# main.net
KiCad netlist of a schematic drawn in Altium Designer
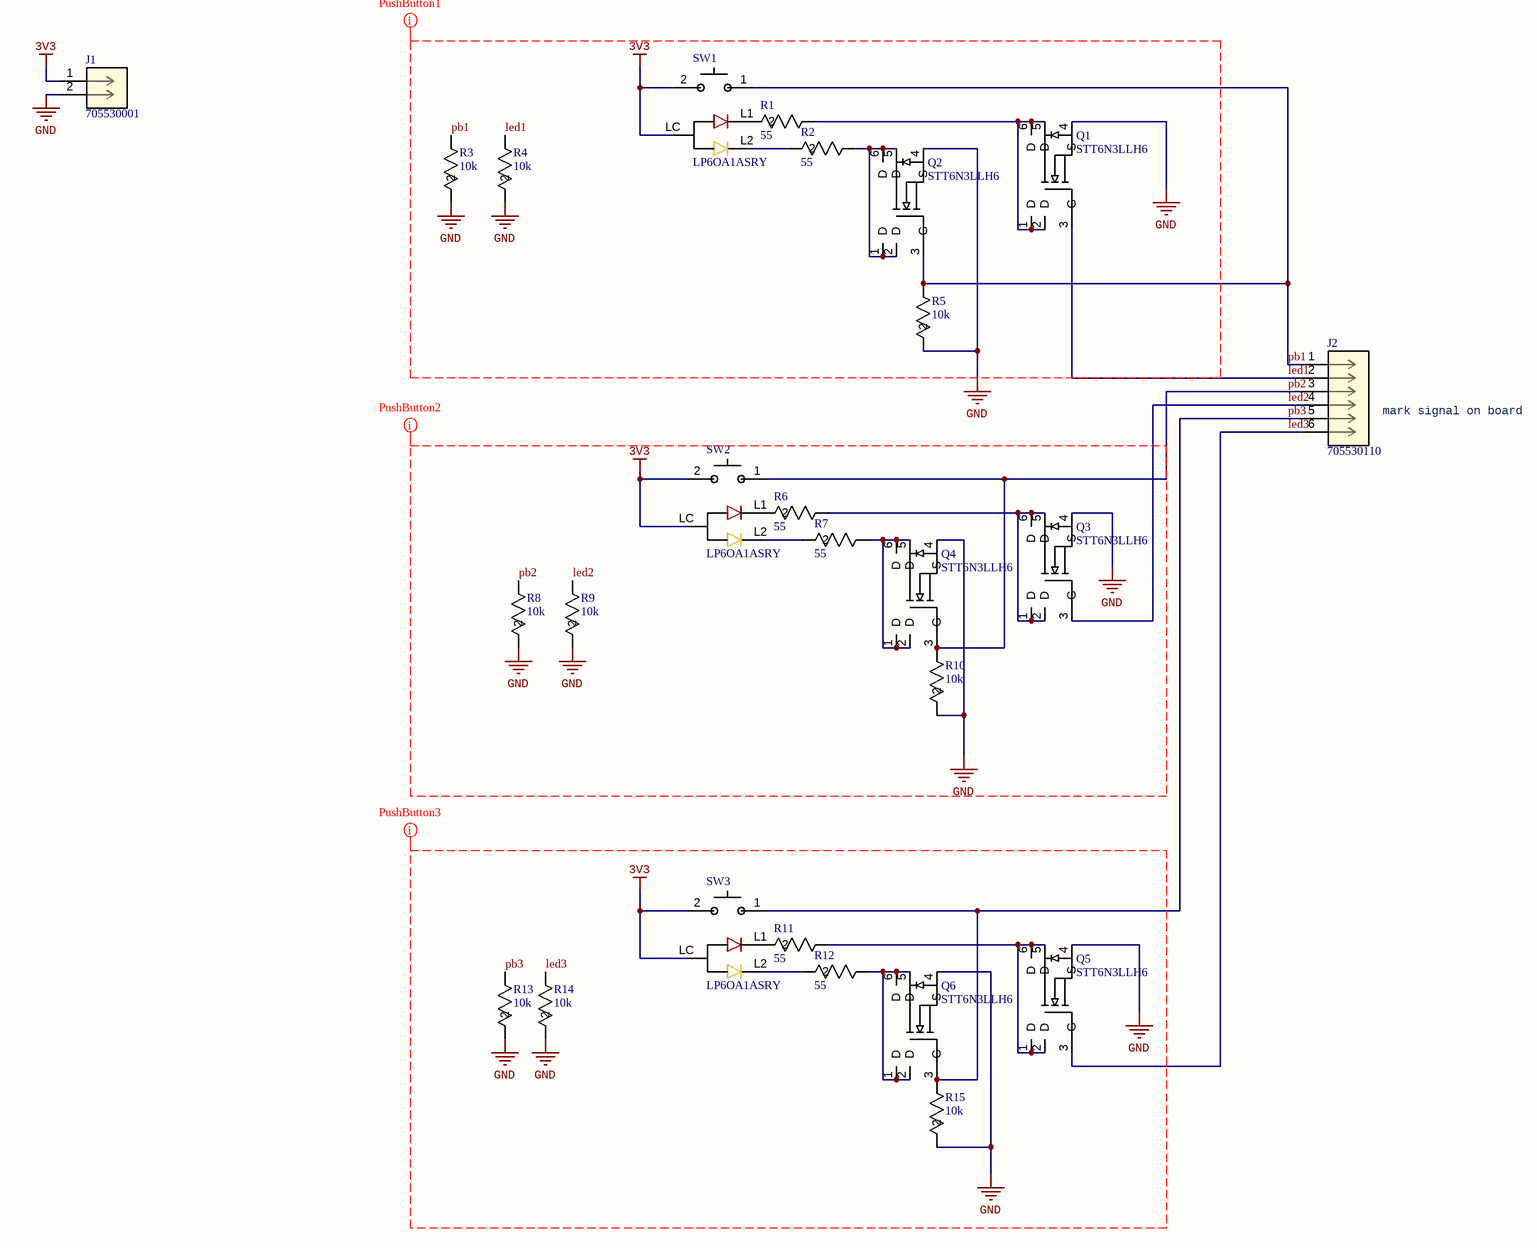
[diagram p0: main.SchDoc]

(export (version "E")
  (design (tool "Eeschema 10.0.6"))
  (components
    (comp (ref "J1")
      (value "705530001")
      (footprint "CONN_705530001_02_MOL")
      (fields (field (name "COPYRIGHT") "Copyright (C) 2025 Ultra Librarian. All rights reserved."))
      (libsource (lib "705530001") (part "705530001"))
    )
    (comp (ref "J2")
      (value "705530110")
      (footprint "CONN_705530005_06_MOL")
      (fields (field (name "COPYRIGHT") "Copyright (C) 2025 Ultra Librarian. All rights reserved."))
      (libsource (lib "705530110") (part "705530110"))
    )
    (comp (ref "Q1")
      (value "STT6N3LLH6")
      (footprint "SOT_6N3LLH6_STM")
      (description "N-channel 30 V, 0.021 Ohm, 6 A STripFET(TM) VI DeepGATE(TM) Power MOSFET in SOT23-6L package")
      (fields (field (name "COPYRIGHT") "Copyright (C) 2026 Ultra Librarian. All rights reserved."))
      (libsource (lib "STT6N3LLH6") (part "STT6N3LLH6"))
    )
    (comp (ref "Q2")
      (value "STT6N3LLH6")
      (footprint "SOT_6N3LLH6_STM")
      (description "N-channel 30 V, 0.021 Ohm, 6 A STripFET(TM) VI DeepGATE(TM) Power MOSFET in SOT23-6L package")
      (fields (field (name "COPYRIGHT") "Copyright (C) 2026 Ultra Librarian. All rights reserved."))
      (libsource (lib "STT6N3LLH6") (part "STT6N3LLH6"))
    )
    (comp (ref "Q3")
      (value "STT6N3LLH6")
      (footprint "SOT_6N3LLH6_STM")
      (description "N-channel 30 V, 0.021 Ohm, 6 A STripFET(TM) VI DeepGATE(TM) Power MOSFET in SOT23-6L package")
      (fields (field (name "COPYRIGHT") "Copyright (C) 2026 Ultra Librarian. All rights reserved."))
      (libsource (lib "STT6N3LLH6") (part "STT6N3LLH6"))
    )
    (comp (ref "Q4")
      (value "STT6N3LLH6")
      (footprint "SOT_6N3LLH6_STM")
      (description "N-channel 30 V, 0.021 Ohm, 6 A STripFET(TM) VI DeepGATE(TM) Power MOSFET in SOT23-6L package")
      (fields (field (name "COPYRIGHT") "Copyright (C) 2026 Ultra Librarian. All rights reserved."))
      (libsource (lib "STT6N3LLH6") (part "STT6N3LLH6"))
    )
    (comp (ref "Q5")
      (value "STT6N3LLH6")
      (footprint "SOT_6N3LLH6_STM")
      (description "N-channel 30 V, 0.021 Ohm, 6 A STripFET(TM) VI DeepGATE(TM) Power MOSFET in SOT23-6L package")
      (fields (field (name "COPYRIGHT") "Copyright (C) 2026 Ultra Librarian. All rights reserved."))
      (libsource (lib "STT6N3LLH6") (part "STT6N3LLH6"))
    )
    (comp (ref "Q6")
      (value "STT6N3LLH6")
      (footprint "SOT_6N3LLH6_STM")
      (description "N-channel 30 V, 0.021 Ohm, 6 A STripFET(TM) VI DeepGATE(TM) Power MOSFET in SOT23-6L package")
      (fields (field (name "COPYRIGHT") "Copyright (C) 2026 Ultra Librarian. All rights reserved."))
      (libsource (lib "STT6N3LLH6") (part "STT6N3LLH6"))
    )
    (comp (ref "R1")
      (value "55")
      (footprint "RC0603N_YAG")
      (description "55 OHM 0.1% 1/10W 0603")
      (fields
        (field (name "MANUFACTURER_PART_NUMBER") "0603 55Ohm")
        (field (name "COPYRIGHT") "Copyright (C) 2026 Ultra Librarian. All rights reserved.")
      )
      (libsource (lib "RT0603BRE07475RL") (part "0603 55Ohm"))
    )
    (comp (ref "R2")
      (value "55")
      (footprint "RC0603N_YAG")
      (description "55 OHM 0.1% 1/10W 0603")
      (fields
        (field (name "MANUFACTURER_PART_NUMBER") "0603 55Ohm")
        (field (name "COPYRIGHT") "Copyright (C) 2026 Ultra Librarian. All rights reserved.")
      )
      (libsource (lib "RT0603BRE07475RL") (part "0603 55Ohm"))
    )
    (comp (ref "R3")
      (value "10k")
      (footprint "RC0603N_YAG")
      (description "10K OHM 0.1% 1/10W 0603")
      (fields
        (field (name "MANUFACTURER_PART_NUMBER") "RT0603BRD0710KL")
        (field (name "COPYRIGHT") "Copyright (C) 2026 Ultra Librarian. All rights reserved.")
      )
      (libsource (lib "RT0603BRE07475RL") (part "RT0603BRD0710KL"))
    )
    (comp (ref "R4")
      (value "10k")
      (footprint "RC0603N_YAG")
      (description "10K OHM 0.1% 1/10W 0603")
      (fields
        (field (name "MANUFACTURER_PART_NUMBER") "RT0603BRD0710KL")
        (field (name "COPYRIGHT") "Copyright (C) 2026 Ultra Librarian. All rights reserved.")
      )
      (libsource (lib "RT0603BRE07475RL") (part "RT0603BRD0710KL"))
    )
    (comp (ref "R5")
      (value "10k")
      (footprint "RC0603N_YAG")
      (description "10K OHM 0.1% 1/10W 0603")
      (fields
        (field (name "MANUFACTURER_PART_NUMBER") "RT0603BRD0710KL")
        (field (name "COPYRIGHT") "Copyright (C) 2026 Ultra Librarian. All rights reserved.")
      )
      (libsource (lib "RT0603BRE07475RL") (part "RT0603BRD0710KL"))
    )
    (comp (ref "R6")
      (value "55")
      (footprint "RC0603N_YAG")
      (description "55 OHM 0.1% 1/10W 0603")
      (fields
        (field (name "MANUFACTURER_PART_NUMBER") "0603 55Ohm")
        (field (name "COPYRIGHT") "Copyright (C) 2026 Ultra Librarian. All rights reserved.")
      )
      (libsource (lib "RT0603BRE07475RL") (part "0603 55Ohm"))
    )
    (comp (ref "R7")
      (value "55")
      (footprint "RC0603N_YAG")
      (description "55 OHM 0.1% 1/10W 0603")
      (fields
        (field (name "MANUFACTURER_PART_NUMBER") "0603 55Ohm")
        (field (name "COPYRIGHT") "Copyright (C) 2026 Ultra Librarian. All rights reserved.")
      )
      (libsource (lib "RT0603BRE07475RL") (part "0603 55Ohm"))
    )
    (comp (ref "R8")
      (value "10k")
      (footprint "RC0603N_YAG")
      (description "10K OHM 0.1% 1/10W 0603")
      (fields
        (field (name "MANUFACTURER_PART_NUMBER") "RT0603BRD0710KL")
        (field (name "COPYRIGHT") "Copyright (C) 2026 Ultra Librarian. All rights reserved.")
      )
      (libsource (lib "RT0603BRE07475RL") (part "RT0603BRD0710KL"))
    )
    (comp (ref "R9")
      (value "10k")
      (footprint "RC0603N_YAG")
      (description "10K OHM 0.1% 1/10W 0603")
      (fields
        (field (name "MANUFACTURER_PART_NUMBER") "RT0603BRD0710KL")
        (field (name "COPYRIGHT") "Copyright (C) 2026 Ultra Librarian. All rights reserved.")
      )
      (libsource (lib "RT0603BRE07475RL") (part "RT0603BRD0710KL"))
    )
    (comp (ref "R10")
      (value "10k")
      (footprint "RC0603N_YAG")
      (description "10K OHM 0.1% 1/10W 0603")
      (fields
        (field (name "MANUFACTURER_PART_NUMBER") "RT0603BRD0710KL")
        (field (name "COPYRIGHT") "Copyright (C) 2026 Ultra Librarian. All rights reserved.")
      )
      (libsource (lib "RT0603BRE07475RL") (part "RT0603BRD0710KL"))
    )
    (comp (ref "R11")
      (value "55")
      (footprint "RC0603N_YAG")
      (description "55 OHM 0.1% 1/10W 0603")
      (fields
        (field (name "MANUFACTURER_PART_NUMBER") "0603 55Ohm")
        (field (name "COPYRIGHT") "Copyright (C) 2026 Ultra Librarian. All rights reserved.")
      )
      (libsource (lib "RT0603BRE07475RL") (part "0603 55Ohm"))
    )
    (comp (ref "R12")
      (value "55")
      (footprint "RC0603N_YAG")
      (description "55 OHM 0.1% 1/10W 0603")
      (fields
        (field (name "MANUFACTURER_PART_NUMBER") "0603 55Ohm")
        (field (name "COPYRIGHT") "Copyright (C) 2026 Ultra Librarian. All rights reserved.")
      )
      (libsource (lib "RT0603BRE07475RL") (part "0603 55Ohm"))
    )
    (comp (ref "R13")
      (value "10k")
      (footprint "RC0603N_YAG")
      (description "10K OHM 0.1% 1/10W 0603")
      (fields
        (field (name "MANUFACTURER_PART_NUMBER") "RT0603BRD0710KL")
        (field (name "COPYRIGHT") "Copyright (C) 2026 Ultra Librarian. All rights reserved.")
      )
      (libsource (lib "RT0603BRE07475RL") (part "RT0603BRD0710KL"))
    )
    (comp (ref "R14")
      (value "10k")
      (footprint "RC0603N_YAG")
      (description "10K OHM 0.1% 1/10W 0603")
      (fields
        (field (name "MANUFACTURER_PART_NUMBER") "RT0603BRD0710KL")
        (field (name "COPYRIGHT") "Copyright (C) 2026 Ultra Librarian. All rights reserved.")
      )
      (libsource (lib "RT0603BRE07475RL") (part "RT0603BRD0710KL"))
    )
    (comp (ref "R15")
      (value "10k")
      (footprint "RC0603N_YAG")
      (description "10K OHM 0.1% 1/10W 0603")
      (fields
        (field (name "MANUFACTURER_PART_NUMBER") "RT0603BRD0710KL")
        (field (name "COPYRIGHT") "Copyright (C) 2026 Ultra Librarian. All rights reserved.")
      )
      (libsource (lib "RT0603BRE07475RL") (part "RT0603BRD0710KL"))
    )
    (comp (ref "SW1")
      (value "LP6OA1ASRY")
      (footprint "LP6")
      (description "LP6 Series Illuminated Pushbutton Switch Momentary SPST Red/Yellow")
      (libsource (lib "LP6OA1ASRY") (part "LP6OA1ASRY"))
    )
    (comp (ref "SW2")
      (value "LP6OA1ASRY")
      (footprint "LP6")
      (description "LP6 Series Illuminated Pushbutton Switch Momentary SPST Red/Yellow")
      (libsource (lib "LP6OA1ASRY") (part "LP6OA1ASRY"))
    )
    (comp (ref "SW3")
      (value "LP6OA1ASRY")
      (footprint "LP6")
      (description "LP6 Series Illuminated Pushbutton Switch Momentary SPST Red/Yellow")
      (libsource (lib "LP6OA1ASRY") (part "LP6OA1ASRY"))
    )
  )
  (nets
    (net (code "1") (name "/led1") (class "Default")
      (node (ref "J2") (pin "2") (pinfunction "2_2") (pintype "passive"))
      (node (ref "Q1") (pin "3") (pinfunction "G_3") (pintype "passive"))
      (node (ref "R4") (pin "1") (pinfunction "1_1") (pintype "passive"))
    )
    (net (code "2") (name "/led2") (class "Default")
      (node (ref "J2") (pin "4") (pinfunction "4_4") (pintype "passive"))
      (node (ref "Q3") (pin "3") (pinfunction "G_3") (pintype "passive"))
      (node (ref "R9") (pin "1") (pinfunction "1_1") (pintype "passive"))
    )
    (net (code "3") (name "/led3") (class "Default")
      (node (ref "J2") (pin "6") (pinfunction "6_6") (pintype "passive"))
      (node (ref "Q5") (pin "3") (pinfunction "G_3") (pintype "passive"))
      (node (ref "R14") (pin "1") (pinfunction "1_1") (pintype "passive"))
    )
    (net (code "4") (name "/pb1") (class "Default")
      (node (ref "J2") (pin "1") (pinfunction "1_1") (pintype "passive"))
      (node (ref "Q2") (pin "3") (pinfunction "G_3") (pintype "passive"))
      (node (ref "R3") (pin "1") (pinfunction "1_1") (pintype "passive"))
      (node (ref "R5") (pin "1") (pinfunction "1_1") (pintype "passive"))
      (node (ref "SW1") (pin "1") (pintype "passive"))
    )
    (net (code "5") (name "/pb2") (class "Default")
      (node (ref "J2") (pin "3") (pinfunction "3_3") (pintype "passive"))
      (node (ref "Q4") (pin "3") (pinfunction "G_3") (pintype "passive"))
      (node (ref "R10") (pin "1") (pinfunction "1_1") (pintype "passive"))
      (node (ref "R8") (pin "1") (pinfunction "1_1") (pintype "passive"))
      (node (ref "SW2") (pin "1") (pintype "passive"))
    )
    (net (code "6") (name "/pb3") (class "Default")
      (node (ref "J2") (pin "5") (pinfunction "5_5") (pintype "passive"))
      (node (ref "Q6") (pin "3") (pinfunction "G_3") (pintype "passive"))
      (node (ref "R13") (pin "1") (pinfunction "1_1") (pintype "passive"))
      (node (ref "R15") (pin "1") (pinfunction "1_1") (pintype "passive"))
      (node (ref "SW3") (pin "1") (pintype "passive"))
    )
    (net (code "7") (name "3V3") (class "Default")
      (node (ref "J1") (pin "1") (pinfunction "1_1") (pintype "passive"))
      (node (ref "SW1") (pin "2") (pintype "passive"))
      (node (ref "SW1") (pin "LC") (pinfunction "red_LC") (pintype "passive"))
      (node (ref "SW2") (pin "2") (pintype "passive"))
      (node (ref "SW2") (pin "LC") (pinfunction "red_LC") (pintype "passive"))
      (node (ref "SW3") (pin "2") (pintype "passive"))
      (node (ref "SW3") (pin "LC") (pinfunction "red_LC") (pintype "passive"))
    )
    (net (code "8") (name "GND") (class "Default")
      (node (ref "J1") (pin "2") (pinfunction "2_2") (pintype "passive"))
      (node (ref "Q1") (pin "4") (pinfunction "S_4") (pintype "passive"))
      (node (ref "Q2") (pin "4") (pinfunction "S_4") (pintype "passive"))
      (node (ref "Q3") (pin "4") (pinfunction "S_4") (pintype "passive"))
      (node (ref "Q4") (pin "4") (pinfunction "S_4") (pintype "passive"))
      (node (ref "Q5") (pin "4") (pinfunction "S_4") (pintype "passive"))
      (node (ref "Q6") (pin "4") (pinfunction "S_4") (pintype "passive"))
      (node (ref "R10") (pin "2") (pinfunction "2_2") (pintype "passive"))
      (node (ref "R13") (pin "2") (pinfunction "2_2") (pintype "passive"))
      (node (ref "R14") (pin "2") (pinfunction "2_2") (pintype "passive"))
      (node (ref "R15") (pin "2") (pinfunction "2_2") (pintype "passive"))
      (node (ref "R3") (pin "2") (pinfunction "2_2") (pintype "passive"))
      (node (ref "R4") (pin "2") (pinfunction "2_2") (pintype "passive"))
      (node (ref "R5") (pin "2") (pinfunction "2_2") (pintype "passive"))
      (node (ref "R8") (pin "2") (pinfunction "2_2") (pintype "passive"))
      (node (ref "R9") (pin "2") (pinfunction "2_2") (pintype "passive"))
    )
    (net (code "9") (name "Net-(Q1-D-Pad1)") (class "Default")
      (node (ref "Q1") (pin "1") (pinfunction "D_1") (pintype "passive"))
      (node (ref "Q1") (pin "2") (pinfunction "D_2") (pintype "passive"))
      (node (ref "Q1") (pin "5") (pinfunction "D_5") (pintype "passive"))
      (node (ref "Q1") (pin "6") (pinfunction "D_6") (pintype "passive"))
      (node (ref "R1") (pin "1") (pinfunction "1_1") (pintype "passive"))
    )
    (net (code "10") (name "Net-(Q2-D-Pad1)") (class "Default")
      (node (ref "Q2") (pin "1") (pinfunction "D_1") (pintype "passive"))
      (node (ref "Q2") (pin "2") (pinfunction "D_2") (pintype "passive"))
      (node (ref "Q2") (pin "5") (pinfunction "D_5") (pintype "passive"))
      (node (ref "Q2") (pin "6") (pinfunction "D_6") (pintype "passive"))
      (node (ref "R2") (pin "1") (pinfunction "1_1") (pintype "passive"))
    )
    (net (code "11") (name "Net-(Q3-D-Pad1)") (class "Default")
      (node (ref "Q3") (pin "1") (pinfunction "D_1") (pintype "passive"))
      (node (ref "Q3") (pin "2") (pinfunction "D_2") (pintype "passive"))
      (node (ref "Q3") (pin "5") (pinfunction "D_5") (pintype "passive"))
      (node (ref "Q3") (pin "6") (pinfunction "D_6") (pintype "passive"))
      (node (ref "R6") (pin "1") (pinfunction "1_1") (pintype "passive"))
    )
    (net (code "12") (name "Net-(Q4-D-Pad1)") (class "Default")
      (node (ref "Q4") (pin "1") (pinfunction "D_1") (pintype "passive"))
      (node (ref "Q4") (pin "2") (pinfunction "D_2") (pintype "passive"))
      (node (ref "Q4") (pin "5") (pinfunction "D_5") (pintype "passive"))
      (node (ref "Q4") (pin "6") (pinfunction "D_6") (pintype "passive"))
      (node (ref "R7") (pin "1") (pinfunction "1_1") (pintype "passive"))
    )
    (net (code "13") (name "Net-(Q5-D-Pad1)") (class "Default")
      (node (ref "Q5") (pin "1") (pinfunction "D_1") (pintype "passive"))
      (node (ref "Q5") (pin "2") (pinfunction "D_2") (pintype "passive"))
      (node (ref "Q5") (pin "5") (pinfunction "D_5") (pintype "passive"))
      (node (ref "Q5") (pin "6") (pinfunction "D_6") (pintype "passive"))
      (node (ref "R11") (pin "1") (pinfunction "1_1") (pintype "passive"))
    )
    (net (code "14") (name "Net-(Q6-D-Pad1)") (class "Default")
      (node (ref "Q6") (pin "1") (pinfunction "D_1") (pintype "passive"))
      (node (ref "Q6") (pin "2") (pinfunction "D_2") (pintype "passive"))
      (node (ref "Q6") (pin "5") (pinfunction "D_5") (pintype "passive"))
      (node (ref "Q6") (pin "6") (pinfunction "D_6") (pintype "passive"))
      (node (ref "R12") (pin "1") (pinfunction "1_1") (pintype "passive"))
    )
    (net (code "15") (name "Net-(R1-Pad2)") (class "Default")
      (node (ref "R1") (pin "2") (pinfunction "2_2") (pintype "passive"))
      (node (ref "SW1") (pin "L1") (pinfunction "red_L1") (pintype "passive"))
    )
    (net (code "16") (name "Net-(R6-Pad2)") (class "Default")
      (node (ref "R6") (pin "2") (pinfunction "2_2") (pintype "passive"))
      (node (ref "SW2") (pin "L1") (pinfunction "red_L1") (pintype "passive"))
    )
    (net (code "17") (name "Net-(R11-Pad2)") (class "Default")
      (node (ref "R11") (pin "2") (pinfunction "2_2") (pintype "passive"))
      (node (ref "SW3") (pin "L1") (pinfunction "red_L1") (pintype "passive"))
    )
    (net (code "18") (name "Net-(SW1-yellow)") (class "Default")
      (node (ref "R2") (pin "2") (pinfunction "2_2") (pintype "passive"))
      (node (ref "SW1") (pin "L2") (pinfunction "yellow_L2") (pintype "passive"))
    )
    (net (code "19") (name "Net-(SW2-yellow)") (class "Default")
      (node (ref "R7") (pin "2") (pinfunction "2_2") (pintype "passive"))
      (node (ref "SW2") (pin "L2") (pinfunction "yellow_L2") (pintype "passive"))
    )
    (net (code "20") (name "Net-(SW3-yellow)") (class "Default")
      (node (ref "R12") (pin "2") (pinfunction "2_2") (pintype "passive"))
      (node (ref "SW3") (pin "L2") (pinfunction "yellow_L2") (pintype "passive"))
    )
  )
)
